# 3_LDO.net
KiCad netlist of a schematic drawn in Altium Designer
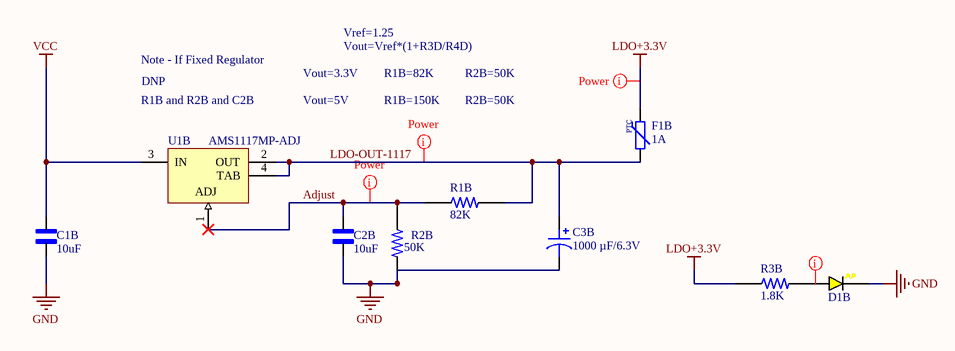
[diagram p0: 3_LDO.SchDoc]

(export (version "E")
  (design (tool "Eeschema 10.0.6"))
  (components
    (comp (ref "C1B")
      (value "10uF")
      (footprint "C-0603")
      (description "Ceramic Capacitor 16V 0603 (1608 Metric)")
      (fields (field (name "MP") "C0603C104J4RAC") (field (name "MF") "KEMET"))
      (libsource (lib "ESP01-S-UART") (part "C-0603"))
    )
    (comp (ref "C2B")
      (value "10uF")
      (footprint "C-0603")
      (description "Ceramic Capacitor 16V 0603 (1608 Metric)")
      (fields (field (name "MP") "C0603C104J4RAC") (field (name "MF") "KEMET"))
      (libsource (lib "ESP01-S-UART") (part "C-0603"))
    )
    (comp (ref "C3B")
      (value "1000 µF/6.3V")
      (footprint "CAP AL TH D8 L3.5 H12.5")
      (description "CAP ALUM 1000UF 20% 6.3V RADIAL")
      (fields
        (field (name "PART NUMBER") "ECA-0JHG102")
        (field (name "MANUFACTURER") "Panasonic Electronic Components")
      )
      (libsource (lib "ESP01-S-UART") (part "Polarised Capacitor"))
    )
    (comp (ref "D1B")
      (value "YELLOW")
      (footprint "LED_0402_YELLOW")
      (description "LED 0402 YELLOW SMD")
      (libsource (lib "ESP01-S-UART") (part "LED_0402_YELLOW"))
    )
    (comp (ref "F1B")
      (value "1A")
      (footprint "FUSE_1206")
      (description "Fuse PPTC SMD 1206")
      (libsource (lib "ESP01-S-UART") (part "FUSE_PPTC_1206"))
    )
    (comp (ref "R1B")
      (value "82K")
      (footprint "R-0603")
      (description "0603")
      (fields (field (name "MP") "2-1623703-0") (field (name "TOLERANCE") "1%"))
      (libsource (lib "ESP01-S-UART") (part "R-0603"))
    )
    (comp (ref "R2B")
      (value "50K")
      (footprint "R-0603")
      (description "0603")
      (fields (field (name "MP") "2-1623703-0") (field (name "TOLERANCE") "1%"))
      (libsource (lib "ESP01-S-UART") (part "R-0603"))
    )
    (comp (ref "R3B")
      (value "1.8K")
      (footprint "R-0603")
      (description "0603")
      (fields (field (name "MP") "2-1623703-0") (field (name "TOLERANCE") "1%"))
      (libsource (lib "ESP01-S-UART") (part "R-0603"))
    )
    (comp (ref "U1B")
      (value "AMS1117MP-ADJ")
      (footprint "MP04A_N")
      (description "800mA Low-Dropout Linear Regulator, 4-pin SOT-223")
      (fields
        (field (name "PARTNUMBER") "LM1117MP-ADJ")
        (field (name "MANUFACTURER") "National Semiconductor")
      )
      (libsource (lib "ESP01-S-UART") (part "PM-REG-LM1086ADJ-SOT4"))
    )
  )
  (nets
    (net (code "1") (name "/Adjust") (class "Default")
      (node (ref "C2B") (pin "2") (pinfunction "2_2") (pintype "passive"))
      (node (ref "R1B") (pin "1") (pinfunction "1_1") (pintype "passive"))
      (node (ref "R2B") (pin "1") (pinfunction "1_1") (pintype "passive"))
      (node (ref "U1B") (pin "1") (pinfunction "ADJ_1") (pintype "input"))
    )
    (net (code "2") (name "/LDO-OUT-1117") (class "Default")
      (node (ref "C3B") (pin "1") (pinfunction "1_1") (pintype "passive"))
      (node (ref "F1B") (pin "1") (pinfunction "1_1") (pintype "passive"))
      (node (ref "R1B") (pin "2") (pinfunction "2_2") (pintype "passive"))
      (node (ref "U1B") (pin "2") (pinfunction "OUT_2") (pintype "power_in"))
      (node (ref "U1B") (pin "4") (pinfunction "TAB_4") (pintype "power_in"))
    )
    (net (code "3") (name "GND") (class "Default")
      (node (ref "C1B") (pin "1") (pinfunction "1_1") (pintype "passive"))
      (node (ref "C2B") (pin "1") (pinfunction "1_1") (pintype "passive"))
      (node (ref "C3B") (pin "2") (pinfunction "2_2") (pintype "passive"))
      (node (ref "D1B") (pin "K") (pinfunction "K_K") (pintype "passive"))
      (node (ref "R2B") (pin "2") (pinfunction "2_2") (pintype "passive"))
    )
    (net (code "4") (name "LDO+3.3V") (class "Default")
      (node (ref "F1B") (pin "2") (pinfunction "2_2") (pintype "passive"))
      (node (ref "R3B") (pin "1") (pinfunction "1_1") (pintype "passive"))
    )
    (net (code "5") (name "Net-(D1B-PadA)") (class "Default")
      (node (ref "D1B") (pin "A") (pinfunction "A_A") (pintype "passive"))
      (node (ref "R3B") (pin "2") (pinfunction "2_2") (pintype "passive"))
    )
    (net (code "6") (name "VCC") (class "Default")
      (node (ref "C1B") (pin "2") (pinfunction "2_2") (pintype "passive"))
      (node (ref "U1B") (pin "3") (pinfunction "IN_3") (pintype "power_in"))
    )
  )
)
